# Main.net
KiCad netlist of a schematic drawn in Altium Designer
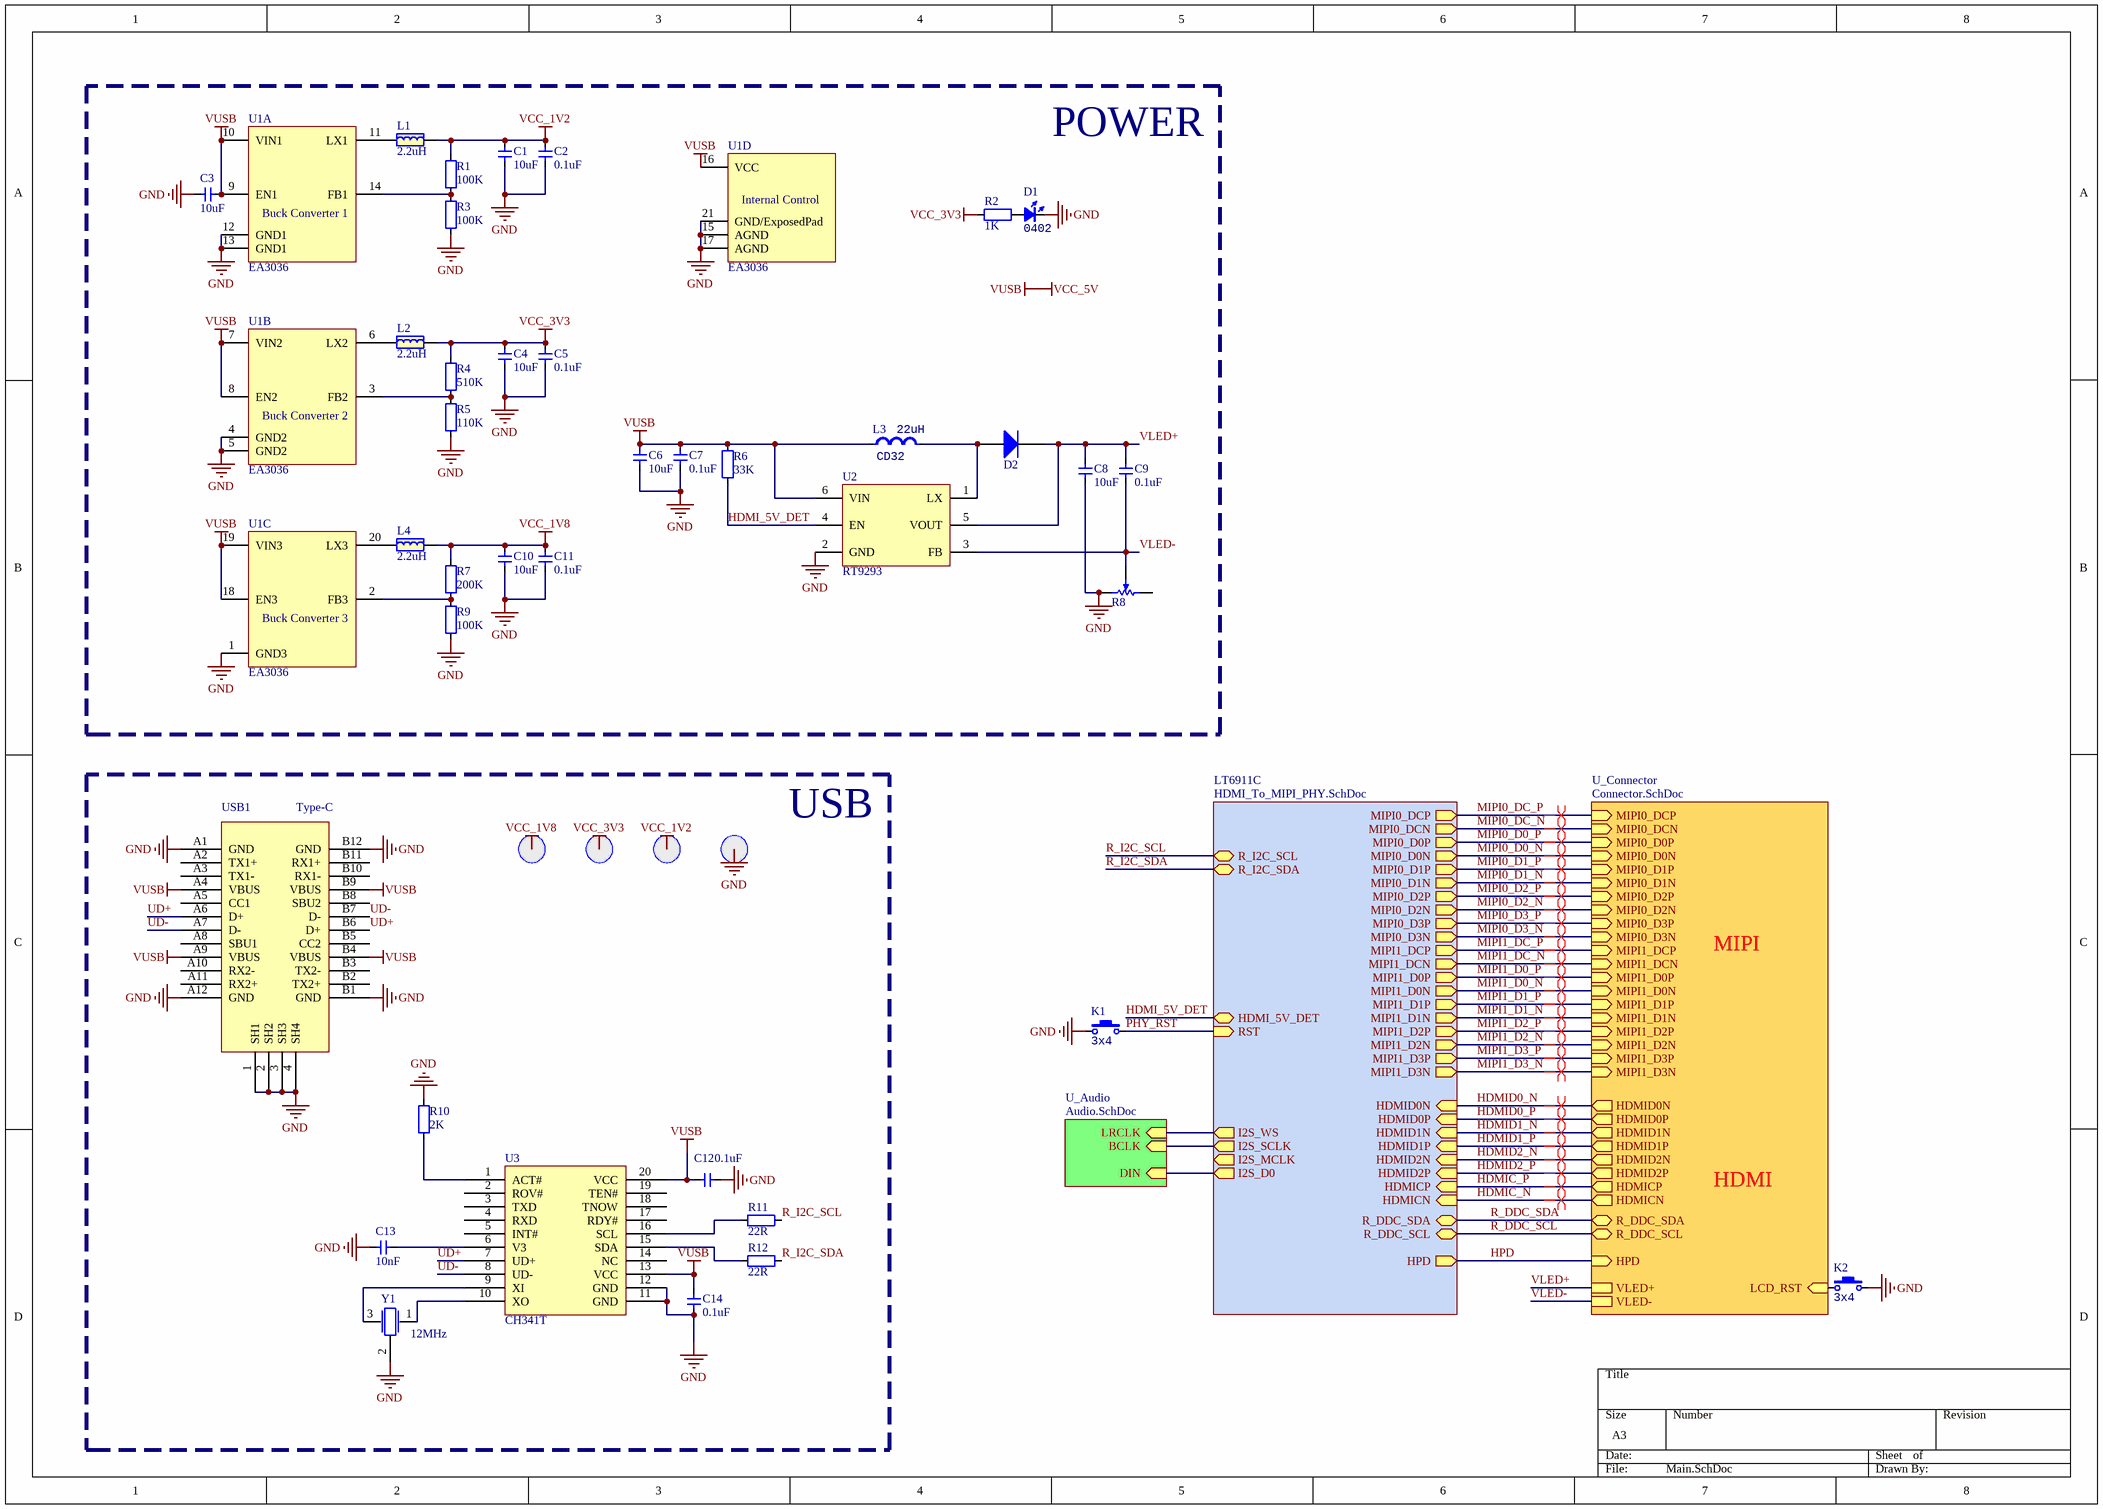
[diagram p0: Main.SchDoc]

(export (version "E")
  (design (tool "Eeschema 10.0.6"))
  (components
    (comp (ref "C1")
      (value "10uF")
      (footprint "CAP_0402")
      (description "Capacitor")
      (libsource (lib "MyPcbLib") (part "电容-0402"))
    )
    (comp (ref "C2")
      (value "0.1uF")
      (footprint "CAP_0402")
      (description "Capacitor")
      (libsource (lib "MyPcbLib") (part "电容-0402"))
    )
    (comp (ref "C3")
      (value "10uF")
      (footprint "CAP_0402")
      (description "Capacitor")
      (libsource (lib "MyPcbLib") (part "电容-0402"))
    )
    (comp (ref "C4")
      (value "10uF")
      (footprint "CAP_0402")
      (description "Capacitor")
      (libsource (lib "MyPcbLib") (part "电容-0402"))
    )
    (comp (ref "C5")
      (value "0.1uF")
      (footprint "CAP_0402")
      (description "Capacitor")
      (libsource (lib "MyPcbLib") (part "电容-0402"))
    )
    (comp (ref "C6")
      (value "10uF")
      (footprint "CAP_0402")
      (description "Capacitor")
      (libsource (lib "MyPcbLib") (part "电容-0402"))
    )
    (comp (ref "C7")
      (value "0.1uF")
      (footprint "CAP_0402")
      (description "Capacitor")
      (libsource (lib "MyPcbLib") (part "电容-0402"))
    )
    (comp (ref "C8")
      (value "10uF")
      (footprint "CAP_0402")
      (description "Capacitor")
      (libsource (lib "MyPcbLib") (part "电容-0402"))
    )
    (comp (ref "C9")
      (value "0.1uF")
      (footprint "CAP_0402")
      (description "Capacitor")
      (libsource (lib "MyPcbLib") (part "电容-0402"))
    )
    (comp (ref "C10")
      (value "10uF")
      (footprint "CAP_0402")
      (description "Capacitor")
      (libsource (lib "MyPcbLib") (part "电容-0402"))
    )
    (comp (ref "C11")
      (value "0.1uF")
      (footprint "CAP_0402")
      (description "Capacitor")
      (libsource (lib "MyPcbLib") (part "电容-0402"))
    )
    (comp (ref "C12")
      (value "0.1uF")
      (footprint "CAP_0402")
      (description "Capacitor")
      (libsource (lib "MyPcbLib") (part "电容-0402"))
    )
    (comp (ref "C13")
      (value "10nF")
      (footprint "CAP_0402")
      (description "Capacitor")
      (libsource (lib "MyPcbLib") (part "电容-0402"))
    )
    (comp (ref "C14")
      (value "0.1uF")
      (footprint "CAP_0402")
      (description "Capacitor")
      (libsource (lib "MyPcbLib") (part "电容-0402"))
    )
    (comp (ref "D1")
      (value "color?")
      (footprint "LED_0402_RED")
      (description "LED")
      (fields (field (name "TYPE") "0402"))
      (libsource (lib "KitSprout") (part "LED_0402"))
    )
    (comp (ref "D2")
      (value "二极管-5B5817WS")
      (footprint "SOD-323")
      (description "40V")
      (libsource (lib "MyPcbLib") (part "二极管-5B5817WS"))
    )
    (comp (ref "K1")
      (value "3x4")
      (footprint "ButtonTACT_3x4x2_180H")
      (description "Button")
      (fields (field (name "Comment") "TACT 2P"))
      (libsource (lib "KitSprout") (part "ButtonTACT_3x4x2_180"))
    )
    (comp (ref "K2")
      (value "3x4")
      (footprint "ButtonTACT_3x4x2_180H")
      (description "Button")
      (fields (field (name "Comment") "TACT 2P"))
      (libsource (lib "KitSprout") (part "ButtonTACT_3x4x2_180"))
    )
    (comp (ref "L1")
      (value "2.2uH")
      (footprint "2520-L")
      (description "磁珠")
      (libsource (lib "MyPcbLib") (part "电感-2520"))
    )
    (comp (ref "L2")
      (value "2.2uH")
      (footprint "2520-L")
      (description "磁珠")
      (libsource (lib "MyPcbLib") (part "电感-2520"))
    )
    (comp (ref "L3")
      (value "22uH")
      (footprint "IND_CD32")
      (description "Inductor")
      (fields (field (name "TYPE") "CD32") (field (name "Comment") "CD32"))
      (libsource (lib "KitSprout") (part "Ind_CD32"))
    )
    (comp (ref "L4")
      (value "2.2uH")
      (footprint "2520-L")
      (description "磁珠")
      (libsource (lib "MyPcbLib") (part "电感-2520"))
    )
    (comp (ref "R1")
      (value "100K")
      (footprint "RES_0402")
      (description "Resistor")
      (libsource (lib "MyPcbLib") (part "电阻-0402"))
    )
    (comp (ref "R2")
      (value "1K")
      (footprint "RES_0402")
      (description "Resistor")
      (libsource (lib "") (part "电阻-0402_1"))
    )
    (comp (ref "R3")
      (value "100K")
      (footprint "RES_0402")
      (description "Resistor")
      (libsource (lib "MyPcbLib") (part "电阻-0402"))
    )
    (comp (ref "R4")
      (value "510K")
      (footprint "RES_0402")
      (description "Resistor")
      (libsource (lib "MyPcbLib") (part "电阻-0402"))
    )
    (comp (ref "R5")
      (value "110K")
      (footprint "RES_0402")
      (description "Resistor")
      (libsource (lib "MyPcbLib") (part "电阻-0402"))
    )
    (comp (ref "R6")
      (value "33K")
      (footprint "RES_0402")
      (description "Resistor")
      (libsource (lib "MyPcbLib") (part "电阻-0402"))
    )
    (comp (ref "R7")
      (value "200K")
      (footprint "RES_0402")
      (description "Resistor")
      (libsource (lib "MyPcbLib") (part "电阻-0402"))
    )
    (comp (ref "R8")
      (value "电位器-贴片")
      (footprint "贴片电位器 3*3")
      (fields (field (name "PUBLISHER") "Altium Limited"))
      (libsource (lib "MyPcbLib") (part "电位器-贴片"))
    )
    (comp (ref "R9")
      (value "100K")
      (footprint "RES_0402")
      (description "Resistor")
      (libsource (lib "MyPcbLib") (part "电阻-0402"))
    )
    (comp (ref "R10")
      (value "2K")
      (footprint "RES_0402")
      (description "Resistor")
      (libsource (lib "") (part "电阻-0402_2"))
    )
    (comp (ref "R11")
      (value "22R")
      (footprint "RES_0402")
      (description "Resistor")
      (libsource (lib "") (part "电阻-0402_1"))
    )
    (comp (ref "R12")
      (value "22R")
      (footprint "RES_0402")
      (description "Resistor")
      (libsource (lib "") (part "电阻-0402_1"))
    )
    (comp (ref "T1") (value "测试点") (footprint "TEST_PT") (libsource (lib "MyPcbLib") (part "测试点")))
    (comp (ref "T2") (value "测试点") (footprint "TEST_PT") (libsource (lib "MyPcbLib") (part "测试点")))
    (comp (ref "T3") (value "测试点") (footprint "TEST_PT") (libsource (lib "MyPcbLib") (part "测试点")))
    (comp (ref "T4") (value "测试点") (footprint "TEST_PT") (libsource (lib "MyPcbLib") (part "测试点")))
    (comp (ref "U1") (value "EA3036") (footprint "QFN-20") (libsource (lib "MyPcbLib") (part "EA3036")))
    (comp (ref "U2")
      (value "RT9293")
      (footprint "SOT23-6")
      (description "LCD-LED Driver")
      (libsource (lib "mLib") (part "RT9293"))
    )
    (comp (ref "U3") (value "CH341T") (footprint "SSOP-20") (libsource (lib "MyPcbLib") (part "CH341T")))
    (comp (ref "USB1")
      (value "Type-C")
      (footprint "Type-C-TOP")
      (libsource (lib "MyPcbLib") (part "USB-Type-C-TOP"))
    )
    (comp (ref "Y1")
      (value "12MHz")
      (footprint "晶振-3P")
      (description "村田贴片")
      (libsource (lib "MyPcbLib") (part "晶振-3Pin"))
    )
  )
  (nets
    (net (code "9") (name "/HDMI_5V_DET") (class "Default")
      (node (ref "R6") (pin "1") (pinfunction "1_1") (pintype "passive"))
      (node (ref "U2") (pin "4") (pinfunction "EN_4") (pintype "passive"))
    )
    (net (code "15") (name "/LCD_RST") (class "Default")
      (node (ref "K2") (pin "1") (pinfunction "1_1") (pintype "passive"))
    )
    (net (code "36") (name "/PHY_RST") (class "Default")
      (node (ref "K1") (pin "2") (pinfunction "2_2") (pintype "passive"))
    )
    (net (code "39") (name "/R_I2C_SCL") (class "Default")
      (node (ref "R11") (pin "2") (pinfunction "2_2") (pintype "passive"))
    )
    (net (code "40") (name "/R_I2C_SDA") (class "Default")
      (node (ref "R12") (pin "2") (pinfunction "2_2") (pintype "passive"))
    )
    (net (code "41") (name "/UD+") (class "Default")
      (node (ref "U3") (pin "7") (pinfunction "UD+_7") (pintype "passive"))
      (node (ref "USB1") (pin "A6") (pinfunction "D+_A6") (pintype "passive"))
      (node (ref "USB1") (pin "B6") (pinfunction "D+_B6") (pintype "passive"))
    )
    (net (code "42") (name "/UD-") (class "Default")
      (node (ref "U3") (pin "8") (pinfunction "UD-_8") (pintype "passive"))
      (node (ref "USB1") (pin "A7") (pinfunction "D-_A7") (pintype "passive"))
      (node (ref "USB1") (pin "B7") (pinfunction "D-_B7") (pintype "passive"))
    )
    (net (code "43") (name "/VLED+") (class "Default")
      (node (ref "C8") (pin "2") (pinfunction "2_2") (pintype "passive"))
      (node (ref "C9") (pin "2") (pinfunction "2_2") (pintype "passive"))
      (node (ref "D2") (pin "2") (pinfunction "K_2") (pintype "passive"))
      (node (ref "U2") (pin "5") (pinfunction "VOUT_5") (pintype "passive"))
    )
    (net (code "44") (name "/VLED-") (class "Default")
      (node (ref "C9") (pin "1") (pinfunction "1_1") (pintype "passive"))
      (node (ref "R8") (pin "3") (pinfunction "W_3") (pintype "passive"))
      (node (ref "U2") (pin "3") (pinfunction "FB_3") (pintype "passive"))
    )
    (net (code "45") (name "GND") (class "Default")
      (node (ref "C1") (pin "2") (pinfunction "2_2") (pintype "passive"))
      (node (ref "C10") (pin "2") (pinfunction "2_2") (pintype "passive"))
      (node (ref "C11") (pin "2") (pinfunction "2_2") (pintype "passive"))
      (node (ref "C12") (pin "2") (pinfunction "2_2") (pintype "passive"))
      (node (ref "C13") (pin "2") (pinfunction "2_2") (pintype "passive"))
      (node (ref "C14") (pin "2") (pinfunction "2_2") (pintype "passive"))
      (node (ref "C2") (pin "2") (pinfunction "2_2") (pintype "passive"))
      (node (ref "C3") (pin "1") (pinfunction "1_1") (pintype "passive"))
      (node (ref "C4") (pin "2") (pinfunction "2_2") (pintype "passive"))
      (node (ref "C5") (pin "2") (pinfunction "2_2") (pintype "passive"))
      (node (ref "C6") (pin "1") (pinfunction "1_1") (pintype "passive"))
      (node (ref "C7") (pin "1") (pinfunction "1_1") (pintype "passive"))
      (node (ref "C8") (pin "1") (pinfunction "1_1") (pintype "passive"))
      (node (ref "D1") (pin "2") (pinfunction "K_2") (pintype "passive"))
      (node (ref "K1") (pin "1") (pinfunction "1_1") (pintype "passive"))
      (node (ref "K2") (pin "2") (pinfunction "2_2") (pintype "passive"))
      (node (ref "R10") (pin "1") (pinfunction "1_1") (pintype "passive"))
      (node (ref "R3") (pin "1") (pinfunction "1_1") (pintype "passive"))
      (node (ref "R5") (pin "1") (pinfunction "1_1") (pintype "passive"))
      (node (ref "R8") (pin "1") (pinfunction "+_1") (pintype "passive"))
      (node (ref "R9") (pin "1") (pinfunction "1_1") (pintype "passive"))
      (node (ref "T4") (pin "0") (pinfunction "0_0") (pintype "passive"))
      (node (ref "U1") (pin "1") (pinfunction "GND3_1") (pintype "power_in"))
      (node (ref "U1") (pin "12") (pinfunction "GND1_12") (pintype "power_in"))
      (node (ref "U1") (pin "13") (pinfunction "GND1_13") (pintype "power_in"))
      (node (ref "U1") (pin "15") (pinfunction "AGND_15") (pintype "power_in"))
      (node (ref "U1") (pin "17") (pinfunction "AGND_17") (pintype "power_in"))
      (node (ref "U1") (pin "21") (pinfunction "GND/ExposedPad_21") (pintype "power_in"))
      (node (ref "U1") (pin "4") (pinfunction "GND2_4") (pintype "power_in"))
      (node (ref "U1") (pin "5") (pinfunction "GND2_5") (pintype "power_in"))
      (node (ref "U2") (pin "2") (pinfunction "GND_2") (pintype "passive"))
      (node (ref "U3") (pin "11") (pinfunction "GND_11") (pintype "passive"))
      (node (ref "U3") (pin "12") (pinfunction "GND_12") (pintype "passive"))
      (node (ref "USB1") (pin "1") (pinfunction "SH1_1") (pintype "passive"))
      (node (ref "USB1") (pin "2") (pinfunction "SH2_2") (pintype "passive"))
      (node (ref "USB1") (pin "3") (pinfunction "SH3_3") (pintype "passive"))
      (node (ref "USB1") (pin "4") (pinfunction "SH4_4") (pintype "passive"))
      (node (ref "USB1") (pin "A1") (pinfunction "GND_A1") (pintype "passive"))
      (node (ref "USB1") (pin "A12") (pinfunction "GND_A12") (pintype "passive"))
      (node (ref "USB1") (pin "B1") (pinfunction "GND_B1") (pintype "passive"))
      (node (ref "USB1") (pin "B12") (pinfunction "GND_B12") (pintype "passive"))
      (node (ref "Y1") (pin "2") (pinfunction "2_2") (pintype "passive"))
    )
    (net (code "46") (name "Net-(D1-A)") (class "Default")
      (node (ref "D1") (pin "1") (pinfunction "A_1") (pintype "passive"))
      (node (ref "R2") (pin "2") (pinfunction "2_2") (pintype "passive"))
    )
    (net (code "47") (name "Net-(D2-A)") (class "Default")
      (node (ref "D2") (pin "1") (pinfunction "A_1") (pintype "passive"))
      (node (ref "L3") (pin "2") (pinfunction "2_2") (pintype "passive"))
      (node (ref "U2") (pin "1") (pinfunction "LX_1") (pintype "passive"))
    )
    (net (code "48") (name "Net-(U1A-FB1)") (class "Default")
      (node (ref "R1") (pin "1") (pinfunction "1_1") (pintype "passive"))
      (node (ref "R3") (pin "2") (pinfunction "2_2") (pintype "passive"))
      (node (ref "U1") (pin "14") (pinfunction "FB1_14") (pintype "passive"))
    )
    (net (code "49") (name "Net-(U1A-LX1)") (class "Default")
      (node (ref "L1") (pin "1") (pintype "passive"))
      (node (ref "U1") (pin "11") (pinfunction "LX1_11") (pintype "passive"))
    )
    (net (code "50") (name "Net-(U1B-FB2)") (class "Default")
      (node (ref "R4") (pin "1") (pinfunction "1_1") (pintype "passive"))
      (node (ref "R5") (pin "2") (pinfunction "2_2") (pintype "passive"))
      (node (ref "U1") (pin "3") (pinfunction "FB2_3") (pintype "passive"))
    )
    (net (code "51") (name "Net-(U1B-LX2)") (class "Default")
      (node (ref "L2") (pin "1") (pintype "passive"))
      (node (ref "U1") (pin "6") (pinfunction "LX2_6") (pintype "passive"))
    )
    (net (code "52") (name "Net-(U1C-FB3)") (class "Default")
      (node (ref "R7") (pin "1") (pinfunction "1_1") (pintype "passive"))
      (node (ref "R9") (pin "2") (pinfunction "2_2") (pintype "passive"))
      (node (ref "U1") (pin "2") (pinfunction "FB3_2") (pintype "passive"))
    )
    (net (code "53") (name "Net-(U1C-LX3)") (class "Default")
      (node (ref "L4") (pin "1") (pintype "passive"))
      (node (ref "U1") (pin "20") (pinfunction "LX3_20") (pintype "passive"))
    )
    (net (code "54") (name "Net-(U3-ACT#)") (class "Default")
      (node (ref "R10") (pin "2") (pinfunction "2_2") (pintype "passive"))
      (node (ref "U3") (pin "1") (pinfunction "ACT#_1") (pintype "passive"))
    )
    (net (code "55") (name "Net-(U3-SCL)") (class "Default")
      (node (ref "R11") (pin "1") (pinfunction "1_1") (pintype "passive"))
      (node (ref "U3") (pin "16") (pinfunction "SCL_16") (pintype "passive"))
    )
    (net (code "56") (name "Net-(U3-SDA)") (class "Default")
      (node (ref "R12") (pin "1") (pinfunction "1_1") (pintype "passive"))
      (node (ref "U3") (pin "15") (pinfunction "SDA_15") (pintype "passive"))
    )
    (net (code "57") (name "Net-(U3-V3)") (class "Default")
      (node (ref "C13") (pin "1") (pinfunction "1_1") (pintype "passive"))
      (node (ref "U3") (pin "6") (pinfunction "V3_6") (pintype "passive"))
    )
    (net (code "58") (name "Net-(U3-XI)") (class "Default")
      (node (ref "U3") (pin "9") (pinfunction "XI_9") (pintype "passive"))
      (node (ref "Y1") (pin "3") (pinfunction "3_3") (pintype "passive"))
    )
    (net (code "59") (name "Net-(U3-XO)") (class "Default")
      (node (ref "U3") (pin "10") (pinfunction "XO_10") (pintype "passive"))
      (node (ref "Y1") (pin "1") (pinfunction "1_1") (pintype "passive"))
    )
    (net (code "60") (name "VCC_1V2") (class "Default")
      (node (ref "C1") (pin "1") (pinfunction "1_1") (pintype "passive"))
      (node (ref "C2") (pin "1") (pinfunction "1_1") (pintype "passive"))
      (node (ref "L1") (pin "2") (pinfunction "2_2") (pintype "passive"))
      (node (ref "R1") (pin "2") (pinfunction "2_2") (pintype "passive"))
      (node (ref "T3") (pin "0") (pinfunction "0_0") (pintype "passive"))
    )
    (net (code "61") (name "VCC_1V8") (class "Default")
      (node (ref "C10") (pin "1") (pinfunction "1_1") (pintype "passive"))
      (node (ref "C11") (pin "1") (pinfunction "1_1") (pintype "passive"))
      (node (ref "L4") (pin "2") (pinfunction "2_2") (pintype "passive"))
      (node (ref "R7") (pin "2") (pinfunction "2_2") (pintype "passive"))
      (node (ref "T1") (pin "0") (pinfunction "0_0") (pintype "passive"))
    )
    (net (code "62") (name "VCC_3V3") (class "Default")
      (node (ref "C4") (pin "1") (pinfunction "1_1") (pintype "passive"))
      (node (ref "C5") (pin "1") (pinfunction "1_1") (pintype "passive"))
      (node (ref "L2") (pin "2") (pinfunction "2_2") (pintype "passive"))
      (node (ref "R2") (pin "1") (pinfunction "1_1") (pintype "passive"))
      (node (ref "R4") (pin "2") (pinfunction "2_2") (pintype "passive"))
      (node (ref "T2") (pin "0") (pinfunction "0_0") (pintype "passive"))
    )
    (net (code "63") (name "VCC_5V") (class "Default")
      (node (ref "C12") (pin "1") (pinfunction "1_1") (pintype "passive"))
      (node (ref "C14") (pin "1") (pinfunction "1_1") (pintype "passive"))
      (node (ref "C3") (pin "2") (pinfunction "2_2") (pintype "passive"))
      (node (ref "C6") (pin "2") (pinfunction "2_2") (pintype "passive"))
      (node (ref "C7") (pin "2") (pinfunction "2_2") (pintype "passive"))
      (node (ref "L3") (pin "1") (pinfunction "1_1") (pintype "passive"))
      (node (ref "R6") (pin "2") (pinfunction "2_2") (pintype "passive"))
      (node (ref "U1") (pin "10") (pinfunction "VIN1_10") (pintype "power_in"))
      (node (ref "U1") (pin "16") (pinfunction "VCC_16") (pintype "power_in"))
      (node (ref "U1") (pin "18") (pinfunction "EN3_18") (pintype "passive"))
      (node (ref "U1") (pin "19") (pinfunction "VIN3_19") (pintype "power_in"))
      (node (ref "U1") (pin "7") (pinfunction "VIN2_7") (pintype "power_in"))
      (node (ref "U1") (pin "8") (pinfunction "EN2_8") (pintype "passive"))
      (node (ref "U1") (pin "9") (pinfunction "EN1_9") (pintype "passive"))
      (node (ref "U2") (pin "6") (pinfunction "VIN_6") (pintype "passive"))
      (node (ref "U3") (pin "13") (pinfunction "VCC_13") (pintype "passive"))
      (node (ref "U3") (pin "20") (pinfunction "VCC_20") (pintype "passive"))
      (node (ref "USB1") (pin "A4") (pinfunction "VBUS_A4") (pintype "passive"))
      (node (ref "USB1") (pin "A9") (pinfunction "VBUS_A9") (pintype "passive"))
      (node (ref "USB1") (pin "B4") (pinfunction "VBUS_B4") (pintype "passive"))
      (node (ref "USB1") (pin "B9") (pinfunction "VBUS_B9") (pintype "passive"))
    )
    (net (code "64") (name "unconnected-(R8---Pad2)") (class "Default")
      (node (ref "R8") (pin "2") (pinfunction "-_2") (pintype "passive"))
    )
    (net (code "65") (name "unconnected-(U3-INT#-Pad5)") (class "Default")
      (node (ref "U3") (pin "5") (pinfunction "INT#_5") (pintype "passive"))
    )
    (net (code "66") (name "unconnected-(U3-NC-Pad14)") (class "Default")
      (node (ref "U3") (pin "14") (pinfunction "NC_14") (pintype "passive"))
    )
    (net (code "67") (name "unconnected-(U3-RDY#-Pad17)") (class "Default")
      (node (ref "U3") (pin "17") (pinfunction "RDY#_17") (pintype "passive"))
    )
    (net (code "68") (name "unconnected-(U3-ROV#-Pad2)") (class "Default")
      (node (ref "U3") (pin "2") (pinfunction "ROV#_2") (pintype "passive"))
    )
    (net (code "69") (name "unconnected-(U3-RXD-Pad4)") (class "Default")
      (node (ref "U3") (pin "4") (pinfunction "RXD_4") (pintype "passive"))
    )
    (net (code "70") (name "unconnected-(U3-TEN#-Pad19)") (class "Default")
      (node (ref "U3") (pin "19") (pinfunction "TEN#_19") (pintype "passive"))
    )
    (net (code "71") (name "unconnected-(U3-TNOW-Pad18)") (class "Default")
      (node (ref "U3") (pin "18") (pinfunction "TNOW_18") (pintype "passive"))
    )
    (net (code "72") (name "unconnected-(U3-TXD-Pad3)") (class "Default")
      (node (ref "U3") (pin "3") (pinfunction "TXD_3") (pintype "passive"))
    )
    (net (code "73") (name "unconnected-(USB1-CC1-PadA5)") (class "Default")
      (node (ref "USB1") (pin "A5") (pinfunction "CC1_A5") (pintype "passive"))
    )
    (net (code "74") (name "unconnected-(USB1-CC2-PadB5)") (class "Default")
      (node (ref "USB1") (pin "B5") (pinfunction "CC2_B5") (pintype "passive"))
    )
    (net (code "75") (name "unconnected-(USB1-RX1+-PadB11)") (class "Default")
      (node (ref "USB1") (pin "B11") (pinfunction "RX1+_B11") (pintype "passive"))
    )
    (net (code "76") (name "unconnected-(USB1-RX1--PadB10)") (class "Default")
      (node (ref "USB1") (pin "B10") (pinfunction "RX1-_B10") (pintype "passive"))
    )
    (net (code "77") (name "unconnected-(USB1-RX2+-PadA11)") (class "Default")
      (node (ref "USB1") (pin "A11") (pinfunction "RX2+_A11") (pintype "passive"))
    )
    (net (code "78") (name "unconnected-(USB1-RX2--PadA10)") (class "Default")
      (node (ref "USB1") (pin "A10") (pinfunction "RX2-_A10") (pintype "passive"))
    )
    (net (code "79") (name "unconnected-(USB1-SBU1-PadA8)") (class "Default")
      (node (ref "USB1") (pin "A8") (pinfunction "SBU1_A8") (pintype "passive"))
    )
    (net (code "80") (name "unconnected-(USB1-SBU2-PadB8)") (class "Default")
      (node (ref "USB1") (pin "B8") (pinfunction "SBU2_B8") (pintype "passive"))
    )
    (net (code "81") (name "unconnected-(USB1-TX1+-PadA2)") (class "Default")
      (node (ref "USB1") (pin "A2") (pinfunction "TX1+_A2") (pintype "passive"))
    )
    (net (code "82") (name "unconnected-(USB1-TX1--PadA3)") (class "Default")
      (node (ref "USB1") (pin "A3") (pinfunction "TX1-_A3") (pintype "passive"))
    )
    (net (code "83") (name "unconnected-(USB1-TX2+-PadB2)") (class "Default")
      (node (ref "USB1") (pin "B2") (pinfunction "TX2+_B2") (pintype "passive"))
    )
    (net (code "84") (name "unconnected-(USB1-TX2--PadB3)") (class "Default")
      (node (ref "USB1") (pin "B3") (pinfunction "TX2-_B3") (pintype "passive"))
    )
  )
)
